# DanielKnapp-th.net
KiCad netlist of a schematic drawn in EAGLE
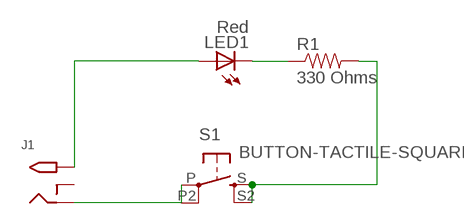
[diagram p0: schematic, sheet 1]

(export (version "E")
  (design (tool "Eeschema 10.0.6"))
  (components
    (comp (ref "J1")
      (value "2.1MMJACKTHM")
      (footprint "eagle-import:PJ-102A")
      (libsource (lib "eagle-import") (part "2.1MMJACKTHM"))
    )
    (comp (ref "LED1")
      (value "Red")
      (footprint "eagle-import:LED5MM")
      (libsource (lib "eagle-import") (part "LED5MM"))
    )
    (comp (ref "R1")
      (value "330 Ohms")
      (footprint "eagle-import:AXIAL-0.3")
      (libsource (lib "eagle-import") (part "RESISTORAXIAL-0.3"))
    )
    (comp (ref "S1")
      (value "BUTTON-TACTILE-SQUARE")
      (footprint "eagle-import:BUTTON-TACTILE-SQUARE-ADAFRUIT1010")
      (libsource (lib "eagle-import") (part "BUTTON-TACTILE-SQUARE"))
    )
  )
  (nets
    (net (code "1") (name "Net-(J1-PadTIP)") (class "Default")
      (node (ref "J1") (pin "TIP") (pinfunction "TIP_TIP") (pintype "bidirectional"))
      (node (ref "LED1") (pin "A") (pinfunction "A_A") (pintype "passive"))
    )
    (net (code "2") (name "Net-(LED1-C)") (class "Default")
      (node (ref "LED1") (pin "K") (pinfunction "C_K") (pintype "passive"))
      (node (ref "R1") (pin "P$1") (pinfunction "1_P$1") (pintype "passive"))
    )
    (net (code "3") (name "Net-(R1-2)") (class "Default")
      (node (ref "R1") (pin "P$2") (pinfunction "2_P$2") (pintype "passive"))
      (node (ref "S1") (pin "S") (pinfunction "S_S") (pintype "passive"))
      (node (ref "S1") (pin "S2") (pinfunction "S1_S2") (pintype "passive"))
    )
    (net (code "4") (name "Net-(S1-P1)") (class "Default")
      (node (ref "J1") (pin "RING") (pinfunction "RING_RING") (pintype "bidirectional"))
      (node (ref "S1") (pin "P") (pinfunction "P_P") (pintype "passive"))
      (node (ref "S1") (pin "P2") (pinfunction "P1_P2") (pintype "passive"))
    )
    (net (code "5") (name "unconnected-(J1-PadRING_SW)") (class "Default")
      (node (ref "J1") (pin "RING_SW") (pinfunction "RING_SW_RING_SW") (pintype "bidirectional"))
    )
  )
)
